# main.net
KiCad netlist of a schematic drawn in Altium Designer
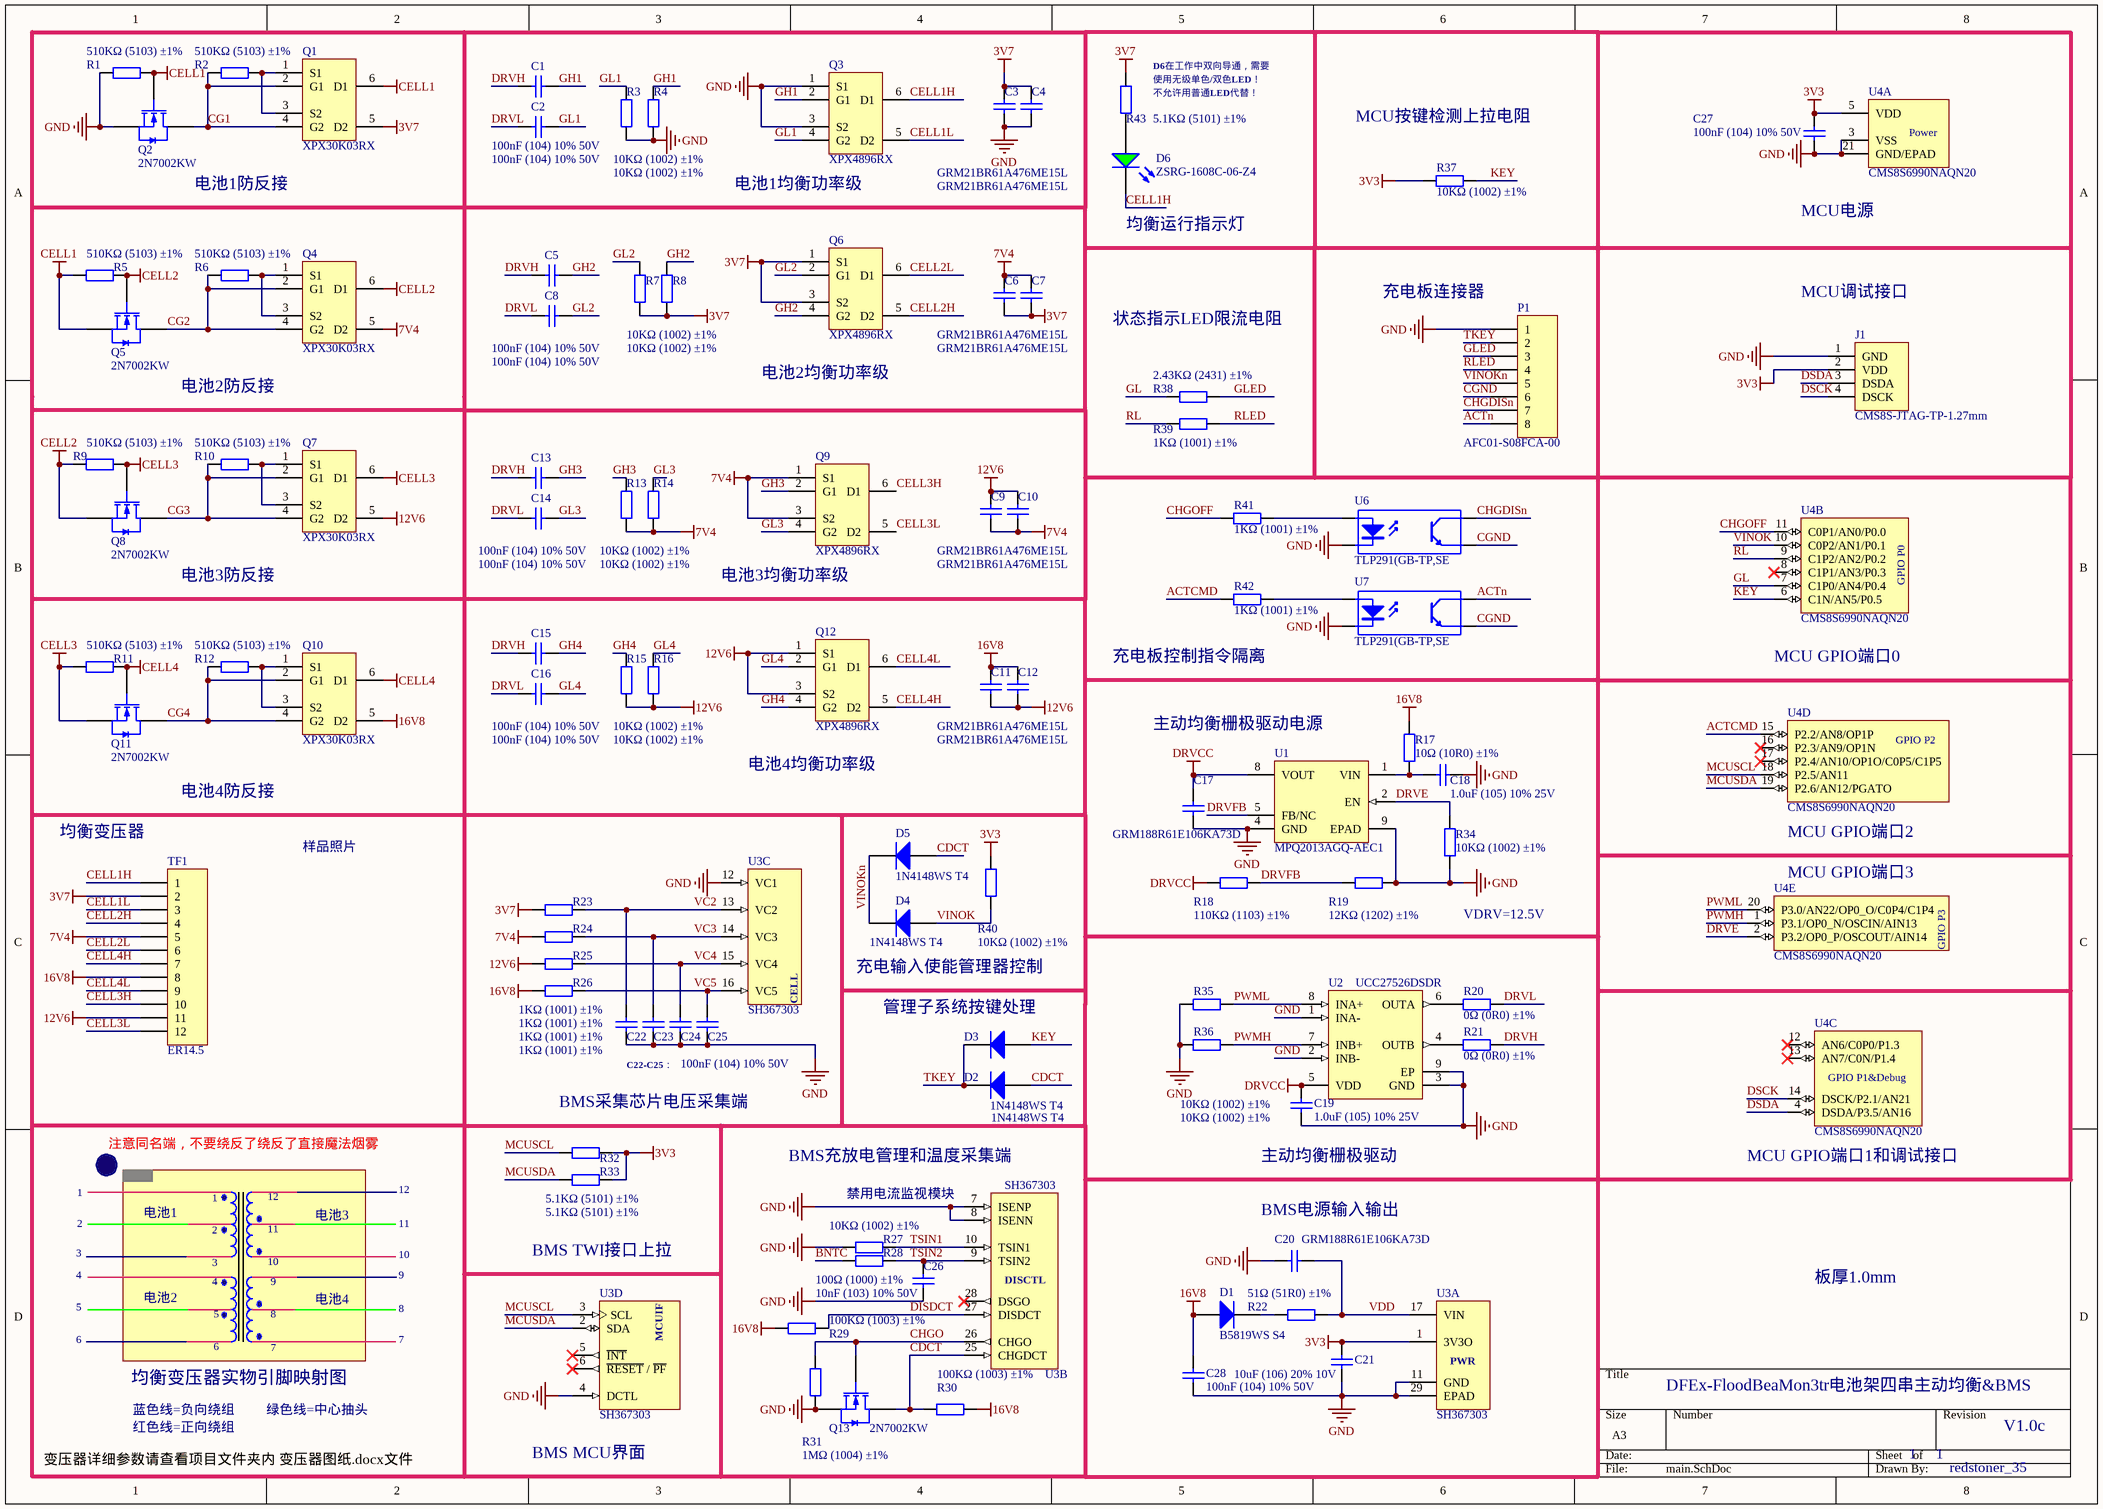
[diagram p0: main.SchDoc]

(export (version "E")
  (design (tool "Eeschema 10.0.6"))
  (components
    (comp (ref "C1")
      (value "100nF (104) 10% 50V")
      (footprint "0402_C")
      (description "贴片电容")
      (libsource (lib "Miscellaneous Devices LC") (part "0402 100nF (104) 10% 16V"))
    )
    (comp (ref "C2")
      (value "100nF (104) 10% 50V")
      (footprint "0402_C")
      (description "贴片电容")
      (libsource (lib "Miscellaneous Devices LC") (part "0402 100nF (104) 10% 16V"))
    )
    (comp (ref "C3")
      (value "GRM21BR61A476ME15L")
      (footprint "0805_C")
      (description "贴片MLCC电容，47uF (476) 20% 10V")
      (libsource (lib "Miscellaneous Devices LC") (part "0805 22uF (226) 20% 25V"))
    )
    (comp (ref "C4")
      (value "GRM21BR61A476ME15L")
      (footprint "0805_C")
      (description "贴片MLCC电容，47uF (476) 20% 10V")
      (libsource (lib "Miscellaneous Devices LC") (part "0805 22uF (226) 20% 25V"))
    )
    (comp (ref "C5")
      (value "100nF (104) 10% 50V")
      (footprint "0402_C")
      (description "贴片电容")
      (libsource (lib "Miscellaneous Devices LC") (part "0402 100nF (104) 10% 16V"))
    )
    (comp (ref "C6")
      (value "GRM21BR61A476ME15L")
      (footprint "0805_C")
      (description "贴片MLCC电容，47uF (476) 20% 10V")
      (libsource (lib "Miscellaneous Devices LC") (part "0805 22uF (226) 20% 25V"))
    )
    (comp (ref "C7")
      (value "GRM21BR61A476ME15L")
      (footprint "0805_C")
      (description "贴片MLCC电容，47uF (476) 20% 10V")
      (libsource (lib "Miscellaneous Devices LC") (part "0805 22uF (226) 20% 25V"))
    )
    (comp (ref "C8")
      (value "100nF (104) 10% 50V")
      (footprint "0402_C")
      (description "贴片电容")
      (libsource (lib "Miscellaneous Devices LC") (part "0402 100nF (104) 10% 16V"))
    )
    (comp (ref "C9")
      (value "GRM21BR61A476ME15L")
      (footprint "0805_C")
      (description "贴片MLCC电容，47uF (476) 20% 10V")
      (libsource (lib "Miscellaneous Devices LC") (part "0805 22uF (226) 20% 25V"))
    )
    (comp (ref "C10")
      (value "GRM21BR61A476ME15L")
      (footprint "0805_C")
      (description "贴片MLCC电容，47uF (476) 20% 10V")
      (libsource (lib "Miscellaneous Devices LC") (part "0805 22uF (226) 20% 25V"))
    )
    (comp (ref "C11")
      (value "GRM21BR61A476ME15L")
      (footprint "0805_C")
      (description "贴片MLCC电容，47uF (476) 20% 10V")
      (libsource (lib "Miscellaneous Devices LC") (part "0805 22uF (226) 20% 25V"))
    )
    (comp (ref "C12")
      (value "GRM21BR61A476ME15L")
      (footprint "0805_C")
      (description "贴片MLCC电容，47uF (476) 20% 10V")
      (libsource (lib "Miscellaneous Devices LC") (part "0805 22uF (226) 20% 25V"))
    )
    (comp (ref "C13")
      (value "100nF (104) 10% 50V")
      (footprint "0402_C")
      (description "贴片电容")
      (libsource (lib "Miscellaneous Devices LC") (part "0402 100nF (104) 10% 16V"))
    )
    (comp (ref "C14")
      (value "100nF (104) 10% 50V")
      (footprint "0402_C")
      (description "贴片电容")
      (libsource (lib "Miscellaneous Devices LC") (part "0402 100nF (104) 10% 16V"))
    )
    (comp (ref "C15")
      (value "100nF (104) 10% 50V")
      (footprint "0402_C")
      (description "贴片电容")
      (libsource (lib "Miscellaneous Devices LC") (part "0402 100nF (104) 10% 16V"))
    )
    (comp (ref "C16")
      (value "100nF (104) 10% 50V")
      (footprint "0402_C")
      (description "贴片电容")
      (libsource (lib "Miscellaneous Devices LC") (part "0402 100nF (104) 10% 16V"))
    )
    (comp (ref "C17")
      (value "GRM188R61E106KA73D")
      (footprint "0603_C")
      (description "0603贴片MLCC电容 10uF ±20% 25V X5R")
      (libsource (lib "Miscellaneous Devices LC") (part "0603 10uF (106) 10% 10V"))
    )
    (comp (ref "C18")
      (value "1.0uF (105) 10% 25V")
      (footprint "0402_C")
      (description "贴片电容")
      (libsource (lib "Miscellaneous Devices LC") (part "0402 1.0uF (105) 10% 25V"))
    )
    (comp (ref "C19")
      (value "1.0uF (105) 10% 25V")
      (footprint "0402_C")
      (description "贴片电容")
      (libsource (lib "Miscellaneous Devices LC") (part "0402 1.0uF (105) 10% 25V"))
    )
    (comp (ref "C20")
      (value "GRM188R61E106KA73D")
      (footprint "0603_C")
      (description "0603贴片MLCC电容 10uF ±20% 25V X5R")
      (libsource (lib "Miscellaneous Devices LC") (part "0603 2.2uF (225) 10% 16V"))
    )
    (comp (ref "C21")
      (value "10uF (106) 20% 10V")
      (footprint "0402_C")
      (description "贴片电容")
      (libsource (lib "Miscellaneous Devices LC") (part "0402 10uF (106) 20% 6.3V"))
    )
    (comp (ref "C22")
      (value "100nF (104) 10% 50V")
      (footprint "0402_C")
      (description "贴片电容")
      (libsource (lib "Miscellaneous Devices LC") (part "0402 100nF (104) 10% 16V"))
    )
    (comp (ref "C23")
      (value "100nF (104) 10% 50V")
      (footprint "0402_C")
      (description "贴片电容")
      (libsource (lib "Miscellaneous Devices LC") (part "0402 100nF (104) 10% 16V"))
    )
    (comp (ref "C24")
      (value "100nF (104) 10% 50V")
      (footprint "0402_C")
      (description "贴片电容")
      (libsource (lib "Miscellaneous Devices LC") (part "0402 100nF (104) 10% 16V"))
    )
    (comp (ref "C25")
      (value "100nF (104) 10% 50V")
      (footprint "0402_C")
      (description "贴片电容")
      (libsource (lib "Miscellaneous Devices LC") (part "0402 100nF (104) 10% 16V"))
    )
    (comp (ref "C26")
      (value "10nF (103) 10% 50V")
      (footprint "0402_C")
      (description "贴片电容")
      (libsource (lib "Miscellaneous Devices LC") (part "0402 10nF (103) 10% 50V"))
    )
    (comp (ref "C27")
      (value "100nF (104) 10% 50V")
      (footprint "0402_C")
      (description "贴片电容")
      (libsource (lib "Miscellaneous Devices LC") (part "0402 100nF (104) 10% 16V"))
    )
    (comp (ref "C28")
      (value "100nF (104) 10% 50V")
      (footprint "0402_C")
      (description "贴片电容")
      (libsource (lib "Miscellaneous Devices LC") (part "0402 100nF (104) 10% 16V"))
    )
    (comp (ref "D1")
      (value "B5819WS S4")
      (footprint "SOD-323")
      (description "二极管")
      (libsource (lib "Miscellaneous Devices LC") (part "SOD-323 1N4148WS T4"))
    )
    (comp (ref "D2")
      (value "1N4148WS T4")
      (footprint "SOD-323")
      (description "二极管")
      (libsource (lib "Miscellaneous Devices LC") (part "SOD-323 1N4148WS T4"))
    )
    (comp (ref "D3")
      (value "1N4148WS T4")
      (footprint "SOD-323")
      (description "二极管")
      (libsource (lib "Miscellaneous Devices LC") (part "SOD-323 1N4148WS T4"))
    )
    (comp (ref "D4")
      (value "1N4148WS T4")
      (footprint "SOD-323")
      (description "二极管")
      (libsource (lib "Miscellaneous Devices LC") (part "SOD-323 1N4148WS T4"))
    )
    (comp (ref "D5")
      (value "1N4148WS T4")
      (footprint "SOD-323")
      (description "二极管")
      (libsource (lib "Miscellaneous Devices LC") (part "SOD-323 1N4148WS T4"))
    )
    (comp (ref "D6")
      (value "ZSRG-1608C-06-Z4")
      (footprint "0603_LED_S1")
      (description "发光二极管 红绿无级双色")
      (libsource (lib "Miscellaneous Devices LC") (part "0603 绿灯"))
    )
    (comp (ref "J1")
      (value "CMS8S-JTAG-TP-1.27mm")
      (footprint "CMS8S-JTAG-TP-1.27")
      (description "面向CMS8S6990NA单片机的调试贴片触点，并不是元器件实物")
      (libsource (lib "custom") (part "CMS8S-JTAG-TP-1.27mm"))
    )
    (comp (ref "P1")
      (value "AFC01-S08FCA-00")
      (footprint "FPC0.5 2H-WS-8P")
      (description "翻盖式下接FPC/FFC连接器 P数:8P 间距:0.5mm")
      (fields (field (name "PUBLISHER") "Altium Limited"))
      (libsource (lib "山猫的集成库20190318") (part "CON 8"))
    )
    (comp (ref "Q1")
      (value "XPX30K03RX")
      (footprint "EDFN3x3")
      (description "双P沟道MOSFET, DFN3x3 -20V -30A 12mΩ")
      (libsource (lib "custom") (part "XPX10H03RX"))
    )
    (comp (ref "Q2")
      (value "2N7002KW")
      (footprint "SC70-3")
      (description "单N沟道MOSFET(场效应管)")
      (libsource (lib "Miscellaneous Devices LC") (part "2N7002 7002"))
    )
    (comp (ref "Q3")
      (value "XPX4896RX")
      (footprint "EDFN3x3")
      (description "双N沟道MOSFET, DFN3x3 40V 45A 7.2mΩ")
      (libsource (lib "custom") (part "XPX10H03RX"))
    )
    (comp (ref "Q4")
      (value "XPX30K03RX")
      (footprint "EDFN3x3")
      (description "双P沟道MOSFET, DFN3x3 -20V -30A 12mΩ")
      (libsource (lib "custom") (part "XPX10H03RX"))
    )
    (comp (ref "Q5")
      (value "2N7002KW")
      (footprint "SC70-3")
      (description "单N沟道MOSFET(场效应管)")
      (libsource (lib "Miscellaneous Devices LC") (part "2N7002 7002"))
    )
    (comp (ref "Q6")
      (value "XPX4896RX")
      (footprint "EDFN3x3")
      (description "双N沟道MOSFET, DFN3x3 40V 45A 7.2mΩ")
      (libsource (lib "custom") (part "XPX10H03RX"))
    )
    (comp (ref "Q7")
      (value "XPX30K03RX")
      (footprint "EDFN3x3")
      (description "双P沟道MOSFET, DFN3x3 -20V -30A 12mΩ")
      (libsource (lib "custom") (part "XPX10H03RX"))
    )
    (comp (ref "Q8")
      (value "2N7002KW")
      (footprint "SC70-3")
      (description "单N沟道MOSFET(场效应管)")
      (libsource (lib "Miscellaneous Devices LC") (part "2N7002 7002"))
    )
    (comp (ref "Q9")
      (value "XPX4896RX")
      (footprint "EDFN3x3")
      (description "双N沟道MOSFET, DFN3x3 40V 45A 7.2mΩ")
      (libsource (lib "custom") (part "XPX10H03RX"))
    )
    (comp (ref "Q10")
      (value "XPX30K03RX")
      (footprint "EDFN3x3")
      (description "双P沟道MOSFET, DFN3x3 -20V -30A 12mΩ")
      (libsource (lib "custom") (part "XPX10H03RX"))
    )
    (comp (ref "Q11")
      (value "2N7002KW")
      (footprint "SC70-3")
      (description "单N沟道MOSFET(场效应管)")
      (libsource (lib "Miscellaneous Devices LC") (part "2N7002 7002"))
    )
    (comp (ref "Q12")
      (value "XPX4896RX")
      (footprint "EDFN3x3")
      (description "双N沟道MOSFET, DFN3x3 40V 45A 7.2mΩ")
      (libsource (lib "custom") (part "XPX10H03RX"))
    )
    (comp (ref "Q13")
      (value "2N7002KW")
      (footprint "SC70-3")
      (description "单N沟道MOSFET(场效应管)")
      (libsource (lib "Miscellaneous Devices LC") (part "2N7002 7002"))
    )
    (comp (ref "R1")
      (value "510KΩ (5103) ±1%")
      (footprint "0402_R")
      (description "贴片电阻")
      (libsource (lib "Miscellaneous Devices LC") (part "0402 510KΩ (5103) 1%"))
    )
    (comp (ref "R2")
      (value "510KΩ (5103) ±1%")
      (footprint "0402_R")
      (description "贴片电阻")
      (libsource (lib "Miscellaneous Devices LC") (part "0402 510KΩ (5103) 1%"))
    )
    (comp (ref "R3")
      (value "10KΩ (1002) ±1%")
      (footprint "0402_R")
      (description "贴片电阻")
      (libsource (lib "") (part "0402 10KΩ (1002) 1%_2"))
    )
    (comp (ref "R4")
      (value "10KΩ (1002) ±1%")
      (footprint "0402_R")
      (description "贴片电阻")
      (libsource (lib "") (part "0402 10KΩ (1002) 1%_2"))
    )
    (comp (ref "R5")
      (value "510KΩ (5103) ±1%")
      (footprint "0402_R")
      (description "贴片电阻")
      (libsource (lib "Miscellaneous Devices LC") (part "0402 510KΩ (5103) 1%"))
    )
    (comp (ref "R6")
      (value "510KΩ (5103) ±1%")
      (footprint "0402_R")
      (description "贴片电阻")
      (libsource (lib "Miscellaneous Devices LC") (part "0402 510KΩ (5103) 1%"))
    )
    (comp (ref "R7")
      (value "10KΩ (1002) ±1%")
      (footprint "0402_R")
      (description "贴片电阻")
      (libsource (lib "Miscellaneous Devices LC") (part "0402 10KΩ (1002) 1%"))
    )
    (comp (ref "R8")
      (value "10KΩ (1002) ±1%")
      (footprint "0402_R")
      (description "贴片电阻")
      (libsource (lib "Miscellaneous Devices LC") (part "0402 10KΩ (1002) 1%"))
    )
    (comp (ref "R9")
      (value "510KΩ (5103) ±1%")
      (footprint "0402_R")
      (description "贴片电阻")
      (libsource (lib "Miscellaneous Devices LC") (part "0402 510KΩ (5103) 1%"))
    )
    (comp (ref "R10")
      (value "510KΩ (5103) ±1%")
      (footprint "0402_R")
      (description "贴片电阻")
      (libsource (lib "Miscellaneous Devices LC") (part "0402 510KΩ (5103) 1%"))
    )
    (comp (ref "R11")
      (value "510KΩ (5103) ±1%")
      (footprint "0402_R")
      (description "贴片电阻")
      (libsource (lib "Miscellaneous Devices LC") (part "0402 510KΩ (5103) 1%"))
    )
    (comp (ref "R12")
      (value "510KΩ (5103) ±1%")
      (footprint "0402_R")
      (description "贴片电阻")
      (libsource (lib "Miscellaneous Devices LC") (part "0402 510KΩ (5103) 1%"))
    )
    (comp (ref "R13")
      (value "10KΩ (1002) ±1%")
      (footprint "0402_R")
      (description "贴片电阻")
      (libsource (lib "Miscellaneous Devices LC") (part "0402 10KΩ (1002) 1%"))
    )
    (comp (ref "R14")
      (value "10KΩ (1002) ±1%")
      (footprint "0402_R")
      (description "贴片电阻")
      (libsource (lib "Miscellaneous Devices LC") (part "0402 10KΩ (1002) 1%"))
    )
    (comp (ref "R15")
      (value "10KΩ (1002) ±1%")
      (footprint "0402_R")
      (description "贴片电阻")
      (libsource (lib "Miscellaneous Devices LC") (part "0402 10KΩ (1002) 1%"))
    )
    (comp (ref "R16")
      (value "10KΩ (1002) ±1%")
      (footprint "0402_R")
      (description "贴片电阻")
      (libsource (lib "Miscellaneous Devices LC") (part "0402 10KΩ (1002) 1%"))
    )
    (comp (ref "R17")
      (value "10Ω (10R0) ±1%")
      (footprint "0402_R")
      (description "贴片电阻")
      (libsource (lib "Miscellaneous Devices LC") (part "0402 10Ω (10R0) 1%"))
    )
    (comp (ref "R18")
      (value "110KΩ (1103) ±1%")
      (footprint "0402_R")
      (description "贴片电阻")
      (libsource (lib "Miscellaneous Devices LC") (part "0402 100KΩ (1003) 1%"))
    )
    (comp (ref "R19")
      (value "12KΩ (1202) ±1%")
      (footprint "0402_R")
      (description "贴片电阻")
      (libsource (lib "Miscellaneous Devices LC") (part "0402 12KΩ (1202) 1%"))
    )
    (comp (ref "R20")
      (value "0Ω (0R0) ±1%")
      (footprint "0402_R")
      (description "贴片电阻")
      (libsource (lib "Miscellaneous Devices LC") (part "0402 0Ω (0R0) 1%"))
    )
    (comp (ref "R21")
      (value "0Ω (0R0) ±1%")
      (footprint "0402_R")
      (description "贴片电阻")
      (libsource (lib "Miscellaneous Devices LC") (part "0402 0Ω (0R0) 1%"))
    )
    (comp (ref "R22")
      (value "51Ω (51R0) ±1%")
      (footprint "0603_R")
      (description "贴片电阻")
      (libsource (lib "Miscellaneous Devices LC") (part "0603 51Ω (51R0) 1%"))
    )
    (comp (ref "R23")
      (value "1KΩ (1001) ±1%")
      (footprint "0402_R")
      (description "贴片电阻")
      (libsource (lib "Miscellaneous Devices LC") (part "0402 1KΩ (1001) 1%"))
    )
    (comp (ref "R24")
      (value "1KΩ (1001) ±1%")
      (footprint "0402_R")
      (description "贴片电阻")
      (libsource (lib "Miscellaneous Devices LC") (part "0402 1KΩ (1001) 1%"))
    )
    (comp (ref "R25")
      (value "1KΩ (1001) ±1%")
      (footprint "0402_R")
      (description "贴片电阻")
      (libsource (lib "Miscellaneous Devices LC") (part "0402 1KΩ (1001) 1%"))
    )
    (comp (ref "R26")
      (value "1KΩ (1001) ±1%")
      (footprint "0402_R")
      (description "贴片电阻")
      (libsource (lib "Miscellaneous Devices LC") (part "0402 1KΩ (1001) 1%"))
    )
    (comp (ref "R27")
      (value "10KΩ (1002) ±1%")
      (footprint "0402_R")
      (description "贴片电阻")
      (libsource (lib "") (part "0402 10KΩ (1002) 1%_1"))
    )
    (comp (ref "R28")
      (value "100Ω (1000) ±1%")
      (footprint "0402_R")
      (description "贴片电阻")
      (libsource (lib "Miscellaneous Devices LC") (part "0402 100Ω (1000) 1%"))
    )
    (comp (ref "R29")
      (value "100KΩ (1003) ±1%")
      (footprint "0402_R")
      (description "贴片电阻")
      (libsource (lib "Miscellaneous Devices LC") (part "0402 100KΩ (1003) 1%"))
    )
    (comp (ref "R30")
      (value "100KΩ (1003) ±1%")
      (footprint "0402_R")
      (description "贴片电阻")
      (libsource (lib "") (part "0402 100KΩ (1003) 1%_1"))
    )
    (comp (ref "R31")
      (value "1MΩ (1004) ±1%")
      (footprint "0402_R")
      (description "贴片电阻")
      (libsource (lib "Miscellaneous Devices LC") (part "0402 1MΩ (1004) 1%"))
    )
    (comp (ref "R32")
      (value "5.1KΩ (5101) ±1%")
      (footprint "0402_R")
      (description "贴片电阻")
      (libsource (lib "Miscellaneous Devices LC") (part "0402 5.1KΩ (5101) 1%"))
    )
    (comp (ref "R33")
      (value "5.1KΩ (5101) ±1%")
      (footprint "0402_R")
      (description "贴片电阻")
      (libsource (lib "Miscellaneous Devices LC") (part "0402 5.1KΩ (5101) 1%"))
    )
    (comp (ref "R34")
      (value "10KΩ (1002) ±1%")
      (footprint "0402_R")
      (description "贴片电阻")
      (libsource (lib "Miscellaneous Devices LC") (part "0402 10KΩ (1002) 1%"))
    )
    (comp (ref "R35")
      (value "10KΩ (1002) ±1%")
      (footprint "0402_R")
      (description "贴片电阻")
      (libsource (lib "") (part "0402 10KΩ (1002) 1%_1"))
    )
    (comp (ref "R36")
      (value "10KΩ (1002) ±1%")
      (footprint "0402_R")
      (description "贴片电阻")
      (libsource (lib "") (part "0402 10KΩ (1002) 1%_1"))
    )
    (comp (ref "R37")
      (value "10KΩ (1002) ±1%")
      (footprint "0402_R")
      (description "贴片电阻")
      (libsource (lib "") (part "0402 10KΩ (1002) 1%_3"))
    )
    (comp (ref "R38")
      (value "2.43KΩ (2431) ±1%")
      (footprint "0402_R")
      (description "贴片电阻")
      (libsource (lib "") (part "0402 2KΩ (2001) 1%_1"))
    )
    (comp (ref "R39")
      (value "1KΩ (1001) ±1%")
      (footprint "0402_R")
      (description "贴片电阻")
      (libsource (lib "Miscellaneous Devices LC") (part "0402 1KΩ (1001) 1%"))
    )
    (comp (ref "R40")
      (value "10KΩ (1002) ±1%")
      (footprint "0402_R")
      (description "贴片电阻")
      (libsource (lib "Miscellaneous Devices LC") (part "0402 10KΩ (1002) 1%"))
    )
    (comp (ref "R41")
      (value "1KΩ (1001) ±1%")
      (footprint "0402_R")
      (description "贴片电阻")
      (libsource (lib "Miscellaneous Devices LC") (part "0402 1KΩ (1001) 1%"))
    )
    (comp (ref "R42")
      (value "1KΩ (1001) ±1%")
      (footprint "0402_R")
      (description "贴片电阻")
      (libsource (lib "Miscellaneous Devices LC") (part "0402 1KΩ (1001) 1%"))
    )
    (comp (ref "R43")
      (value "5.1KΩ (5101) ±1%")
      (footprint "0402_R")
      (description "贴片电阻")
      (libsource (lib "Miscellaneous Devices LC") (part "0402 2KΩ (2001) 1%"))
    )
    (comp (ref "TF1")
      (value "ER14.5")
      (footprint "ER14.5 SMT6+6")
      (description "ER14.5定制均衡变压器，PC40磁芯")
      (fields (field (name "PUBLISHER") "Altium Limited"))
      (libsource (lib "山猫的集成库20190318") (part "CON 12"))
    )
    (comp (ref "U1")
      (value "MPQ2013AGQ-AEC1")
      (footprint "MPQ2013A-QFN8")
      (description "MPS 40V LDO with Enable pin QFN3x3 package")
      (libsource (lib "custom") (part "MPQ2013AGQ-xx-AEC1"))
    )
    (comp (ref "U2")
      (value "UCC27526DSDR")
      (footprint "DSD0008D")
      (description "双路18V 5A峰值电流低侧栅极驱动器，WSON-8封装尺寸")
      (libsource (lib "custom") (part "UCC27526DSDR"))
    )
    (comp (ref "U3")
      (value "SH367303")
      (footprint "QFN28-5x5")
      (description "3至5串锂离子电池BMS模拟前端，具备充放电控制/电压采集和I2C接口")
      (libsource (lib "custom") (part "SH367303"))
    )
    (comp (ref "U4")
      (value "CMS8S6990NAQN20")
      (footprint "QFN40P300X300X800_HS-21N")
      (description "增强型闪存1T 8051单片机，16KB Flash 256+1K XRAM")
      (libsource (lib "custom") (part "CM8S6990NA-QFN20"))
    )
    (comp (ref "U6")
      (value "TLP291(GB-TP,SE")
      (footprint "SOP127P700X210-4M")
      (description "DC输入光电耦合隔离器，线性输入输出，隔离电压(rms):3750V SOP-4小型封装")
      (fields (field (name "PUBLISHER") "Altium Limited"))
      (libsource (lib "Miscellaneous Devices") (part "Optoisolator1"))
    )
    (comp (ref "U7")
      (value "TLP291(GB-TP,SE")
      (footprint "SOP127P700X210-4M")
      (description "DC输入光电耦合隔离器，线性输入输出，隔离电压(rms):3750V SOP-4小型封装")
      (fields (field (name "PUBLISHER") "Altium Limited"))
      (libsource (lib "Miscellaneous Devices") (part "Optoisolator1"))
    )
  )
  (nets
    (net (code "1") (name "/ACTCMD") (class "Default")
      (node (ref "R42") (pin "1") (pinfunction "1_1") (pintype "passive"))
      (node (ref "U4") (pin "15") (pinfunction "P2.2/AN8/OP1P_15") (pintype "bidirectional"))
    )
    (net (code "2") (name "/ACTn") (class "Default")
      (node (ref "P1") (pin "8") (pinfunction "8_8") (pintype "passive"))
      (node (ref "U7") (pin "4") (pinfunction "C_4") (pintype "passive"))
    )
    (net (code "3") (name "/BNTC") (class "Default")
      (node (ref "R28") (pin "1") (pinfunction "1_1") (pintype "passive"))
    )
    (net (code "4") (name "/CDCT") (class "Default")
      (node (ref "D2") (pin "1") (pinfunction "A_1") (pintype "passive"))
      (node (ref "D5") (pin "1") (pinfunction "A_1") (pintype "passive"))
      (node (ref "Q13") (pin "3") (pinfunction "D_3") (pintype "passive"))
      (node (ref "R30") (pin "2") (pinfunction "2_2") (pintype "passive"))
      (node (ref "U3") (pin "25") (pinfunction "CHGDCT_25") (pintype "input"))
    )
    (net (code "5") (name "/CELL1H") (class "Default")
      (node (ref "D6") (pin "K") (pinfunction "K_K") (pintype "passive"))
      (node (ref "Q3") (pin "6") (pinfunction "D1_6") (pintype "passive"))
      (node (ref "TF1") (pin "1") (pinfunction "1_1") (pintype "passive"))
    )
    (net (code "6") (name "/CELL1L") (class "Default")
      (node (ref "Q3") (pin "5") (pinfunction "D2_5") (pintype "passive"))
      (node (ref "TF1") (pin "3") (pinfunction "3_3") (pintype "passive"))
    )
    (net (code "7") (name "/CELL2H") (class "Default")
      (node (ref "Q6") (pin "5") (pinfunction "D2_5") (pintype "passive"))
      (node (ref "TF1") (pin "4") (pinfunction "4_4") (pintype "passive"))
    )
    (net (code "8") (name "/CELL2L") (class "Default")
      (node (ref "Q6") (pin "6") (pinfunction "D1_6") (pintype "passive"))
      (node (ref "TF1") (pin "6") (pinfunction "6_6") (pintype "passive"))
    )
    (net (code "9") (name "/CELL3H") (class "Default")
      (node (ref "Q9") (pin "6") (pinfunction "D1_6") (pintype "passive"))
      (node (ref "TF1") (pin "10") (pinfunction "10_10") (pintype "passive"))
    )
    (net (code "10") (name "/CELL3L") (class "Default")
      (node (ref "Q9") (pin "5") (pinfunction "D2_5") (pintype "passive"))
      (node (ref "TF1") (pin "12") (pinfunction "12_12") (pintype "passive"))
    )
    (net (code "11") (name "/CELL4H") (class "Default")
      (node (ref "Q12") (pin "5") (pinfunction "D2_5") (pintype "passive"))
      (node (ref "TF1") (pin "7") (pinfunction "7_7") (pintype "passive"))
    )
    (net (code "12") (name "/CELL4L") (class "Default")
      (node (ref "Q12") (pin "6") (pinfunction "D1_6") (pintype "passive"))
      (node (ref "TF1") (pin "9") (pinfunction "9_9") (pintype "passive"))
    )
    (net (code "13") (name "/CG1") (class "Default")
      (node (ref "Q1") (pin "2") (pinfunction "G1_2") (pintype "passive"))
      (node (ref "Q1") (pin "4") (pinfunction "G2_4") (pintype "passive"))
      (node (ref "Q2") (pin "3") (pinfunction "D_3") (pintype "passive"))
      (node (ref "R2") (pin "1") (pinfunction "1_1") (pintype "passive"))
    )
    (net (code "14") (name "/CG2") (class "Default")
      (node (ref "Q4") (pin "2") (pinfunction "G1_2") (pintype "passive"))
      (node (ref "Q4") (pin "4") (pinfunction "G2_4") (pintype "passive"))
      (node (ref "Q5") (pin "3") (pinfunction "D_3") (pintype "passive"))
      (node (ref "R6") (pin "1") (pinfunction "1_1") (pintype "passive"))
    )
    (net (code "15") (name "/CG3") (class "Default")
      (node (ref "Q7") (pin "2") (pinfunction "G1_2") (pintype "passive"))
      (node (ref "Q7") (pin "4") (pinfunction "G2_4") (pintype "passive"))
      (node (ref "Q8") (pin "3") (pinfunction "D_3") (pintype "passive"))
      (node (ref "R10") (pin "1") (pinfunction "1_1") (pintype "passive"))
    )
    (net (code "16") (name "/CG4") (class "Default")
      (node (ref "Q10") (pin "2") (pinfunction "G1_2") (pintype "passive"))
      (node (ref "Q10") (pin "4") (pinfunction "G2_4") (pintype "passive"))
      (node (ref "Q11") (pin "3") (pinfunction "D_3") (pintype "passive"))
      (node (ref "R12") (pin "1") (pinfunction "1_1") (pintype "passive"))
    )
    (net (code "17") (name "/CGND") (class "Default")
      (node (ref "P1") (pin "6") (pinfunction "6_6") (pintype "passive"))
      (node (ref "U6") (pin "3") (pinfunction "E_3") (pintype "passive"))
      (node (ref "U7") (pin "3") (pinfunction "E_3") (pintype "passive"))
    )
    (net (code "18") (name "/CHGDISn") (class "Default")
      (node (ref "P1") (pin "7") (pinfunction "7_7") (pintype "passive"))
      (node (ref "U6") (pin "4") (pinfunction "C_4") (pintype "passive"))
    )
    (net (code "19") (name "/CHGO") (class "Default")
      (node (ref "Q13") (pin "1") (pinfunction "G_1") (pintype "passive"))
      (node (ref "R31") (pin "2") (pinfunction "2_2") (pintype "passive"))
      (node (ref "U3") (pin "26") (pinfunction "CHGO_26") (pintype "output"))
    )
    (net (code "20") (name "/CHGOFF") (class "Default")
      (node (ref "R41") (pin "1") (pinfunction "1_1") (pintype "passive"))
      (node (ref "U4") (pin "11") (pinfunction "C0P1/AN0/P0.0_11") (pintype "bidirectional"))
    )
    (net (code "21") (name "/DISDCT") (class "Default")
      (node (ref "R29") (pin "2") (pinfunction "2_2") (pintype "passive"))
      (node (ref "U3") (pin "27") (pinfunction "DISDCT_27") (pintype "input"))
    )
    (net (code "22") (name "/DRVE") (class "Default")
      (node (ref "R34") (pin "2") (pinfunction "2_2") (pintype "passive"))
      (node (ref "U1") (pin "2") (pinfunction "EN_2") (pintype "input"))
      (node (ref "U4") (pin "2") (pinfunction "P3.2/OP0_P/OSCOUT/AIN14_2") (pintype "bidirectional"))
    )
    (net (code "23") (name "/DRVFB") (class "Default")
      (node (ref "R18") (pin "2") (pinfunction "2_2") (pintype "passive"))
      (node (ref "R19") (pin "1") (pinfunction "1_1") (pintype "passive"))
      (node (ref "U1") (pin "5") (pinfunction "FB/NC_5") (pintype "passive"))
    )
    (net (code "24") (name "/DRVH") (class "Default")
      (node (ref "C1") (pin "1") (pinfunction "1_1") (pintype "passive"))
      (node (ref "C13") (pin "1") (pinfunction "1_1") (pintype "passive"))
      (node (ref "C15") (pin "1") (pinfunction "1_1") (pintype "passive"))
      (node (ref "C5") (pin "1") (pinfunction "1_1") (pintype "passive"))
      (node (ref "R21") (pin "2") (pinfunction "2_2") (pintype "passive"))
    )
    (net (code "25") (name "/DRVL") (class "Default")
      (node (ref "C14") (pin "1") (pinfunction "1_1") (pintype "passive"))
      (node (ref "C16") (pin "1") (pinfunction "1_1") (pintype "passive"))
      (node (ref "C2") (pin "1") (pinfunction "1_1") (pintype "passive"))
      (node (ref "C8") (pin "1") (pinfunction "1_1") (pintype "passive"))
      (node (ref "R20") (pin "2") (pinfunction "2_2") (pintype "passive"))
    )
    (net (code "26") (name "/DSCK") (class "Default")
      (node (ref "J1") (pin "4") (pinfunction "DSCK_4") (pintype "passive"))
      (node (ref "U4") (pin "14") (pinfunction "DSCK/P2.1/AN21_14") (pintype "bidirectional"))
    )
    (net (code "27") (name "/DSDA") (class "Default")
      (node (ref "J1") (pin "3") (pinfunction "DSDA_3") (pintype "passive"))
      (node (ref "U4") (pin "4") (pinfunction "DSDA/P3.5/AN16_4") (pintype "bidirectional"))
    )
    (net (code "28") (name "/GH1") (class "Default")
      (node (ref "C1") (pin "2") (pinfunction "2_2") (pintype "passive"))
      (node (ref "Q3") (pin "2") (pinfunction "G1_2") (pintype "passive"))
      (node (ref "R4") (pin "1") (pinfunction "1_1") (pintype "passive"))
    )
    (net (code "29") (name "/GH2") (class "Default")
      (node (ref "C5") (pin "2") (pinfunction "2_2") (pintype "passive"))
      (node (ref "Q6") (pin "4") (pinfunction "G2_4") (pintype "passive"))
      (node (ref "R8") (pin "2") (pinfunction "2_2") (pintype "passive"))
    )
    (net (code "30") (name "/GH3") (class "Default")
      (node (ref "C13") (pin "2") (pinfunction "2_2") (pintype "passive"))
      (node (ref "Q9") (pin "2") (pinfunction "G1_2") (pintype "passive"))
      (node (ref "R13") (pin "2") (pinfunction "2_2") (pintype "passive"))
    )
    (net (code "31") (name "/GH4") (class "Default")
      (node (ref "C15") (pin "2") (pinfunction "2_2") (pintype "passive"))
      (node (ref "Q12") (pin "4") (pinfunction "G2_4") (pintype "passive"))
      (node (ref "R15") (pin "2") (pinfunction "2_2") (pintype "passive"))
    )
    (net (code "32") (name "/GL") (class "Default")
      (node (ref "R38") (pin "1") (pinfunction "1_1") (pintype "passive"))
      (node (ref "U4") (pin "7") (pinfunction "C1P0/AN4/P0.4_7") (pintype "bidirectional"))
    )
    (net (code "33") (name "/GL1") (class "Default")
      (node (ref "C2") (pin "2") (pinfunction "2_2") (pintype "passive"))
      (node (ref "Q3") (pin "4") (pinfunction "G2_4") (pintype "passive"))
      (node (ref "R3") (pin "1") (pinfunction "1_1") (pintype "passive"))
    )
    (net (code "34") (name "/GL2") (class "Default")
      (node (ref "C8") (pin "2") (pinfunction "2_2") (pintype "passive"))
      (node (ref "Q6") (pin "2") (pinfunction "G1_2") (pintype "passive"))
      (node (ref "R7") (pin "2") (pinfunction "2_2") (pintype "passive"))
    )
    (net (code "35") (name "/GL3") (class "Default")
      (node (ref "C14") (pin "2") (pinfunction "2_2") (pintype "passive"))
      (node (ref "Q9") (pin "4") (pinfunction "G2_4") (pintype "passive"))
      (node (ref "R14") (pin "2") (pinfunction "2_2") (pintype "passive"))
    )
    (net (code "36") (name "/GL4") (class "Default")
      (node (ref "C16") (pin "2") (pinfunction "2_2") (pintype "passive"))
      (node (ref "Q12") (pin "2") (pinfunction "G1_2") (pintype "passive"))
      (node (ref "R16") (pin "2") (pinfunction "2_2") (pintype "passive"))
    )
    (net (code "37") (name "/GLED") (class "Default")
      (node (ref "P1") (pin "3") (pinfunction "3_3") (pintype "passive"))
      (node (ref "R38") (pin "2") (pinfunction "2_2") (pintype "passive"))
    )
    (net (code "38") (name "/KEY") (class "Default")
      (node (ref "D3") (pin "1") (pinfunction "A_1") (pintype "passive"))
      (node (ref "R37") (pin "2") (pinfunction "2_2") (pintype "passive"))
      (node (ref "U4") (pin "6") (pinfunction "C1N/AN5/P0.5_6") (pintype "bidirectional"))
    )
    (net (code "39") (name "/MCUSCL") (class "Default")
      (node (ref "R32") (pin "1") (pinfunction "1_1") (pintype "passive"))
      (node (ref "U3") (pin "3") (pinfunction "SCL_3") (pintype "input"))
      (node (ref "U4") (pin "18") (pinfunction "P2.5/AN11_18") (pintype "bidirectional"))
    )
    (net (code "40") (name "/MCUSDA") (class "Default")
      (node (ref "R33") (pin "1") (pinfunction "1_1") (pintype "passive"))
      (node (ref "U3") (pin "2") (pinfunction "SDA_2") (pintype "bidirectional"))
      (node (ref "U4") (pin "19") (pinfunction "P2.6/AN12/PGATO_19") (pintype "bidirectional"))
    )
    (net (code "41") (name "/PWMH") (class "Default")
      (node (ref "R36") (pin "1") (pinfunction "1_1") (pintype "passive"))
      (node (ref "U2") (pin "7") (pinfunction "INB+_7") (pintype "input"))
      (node (ref "U4") (pin "1") (pinfunction "P3.1/OP0_N/OSCIN/AIN13_1") (pintype "bidirectional"))
    )
    (net (code "42") (name "/PWML") (class "Default")
      (node (ref "R35") (pin "1") (pinfunction "1_1") (pintype "passive"))
      (node (ref "U2") (pin "8") (pinfunction "INA+_8") (pintype "input"))
      (node (ref "U4") (pin "20") (pinfunction "P3.0/AN22/OP0_O/C0P4/C1P4_20") (pintype "bidirectional"))
    )
    (net (code "43") (name "/RL") (class "Default")
      (node (ref "R39") (pin "1") (pinfunction "1_1") (pintype "passive"))
      (node (ref "U4") (pin "9") (pinfunction "C1P2/AN2/P0.2_9") (pintype "bidirectional"))
    )
    (net (code "44") (name "/RLED") (class "Default")
      (node (ref "P1") (pin "4") (pinfunction "4_4") (pintype "passive"))
      (node (ref "R39") (pin "2") (pinfunction "2_2") (pintype "passive"))
    )
    (net (code "45") (name "/TKEY") (class "Default")
      (node (ref "D2") (pin "2") (pinfunction "K_2") (pintype "passive"))
      (node (ref "D3") (pin "2") (pinfunction "K_2") (pintype "passive"))
      (node (ref "P1") (pin "2") (pinfunction "2_2") (pintype "passive"))
    )
    (net (code "46") (name "/TSIN1") (class "Default")
      (node (ref "R27") (pin "1") (pinfunction "1_1") (pintype "passive"))
      (node (ref "U3") (pin "10") (pinfunction "TSIN1_10") (pintype "input"))
    )
    (net (code "47") (name "/TSIN2") (class "Default")
      (node (ref "C26") (pin "2") (pinfunction "2_2") (pintype "passive"))
      (node (ref "R28") (pin "2") (pinfunction "2_2") (pintype "passive"))
      (node (ref "U3") (pin "9") (pinfunction "TSIN2_9") (pintype "input"))
    )
    (net (code "48") (name "/VC2") (class "Default")
      (node (ref "C22") (pin "2") (pinfunction "2_2") (pintype "passive"))
      (node (ref "R23") (pin "2") (pinfunction "2_2") (pintype "passive"))
      (node (ref "U3") (pin "13") (pinfunction "VC2_13") (pintype "input"))
    )
    (net (code "49") (name "/VC3") (class "Default")
      (node (ref "C23") (pin "2") (pinfunction "2_2") (pintype "passive"))
      (node (ref "R24") (pin "2") (pinfunction "2_2") (pintype "passive"))
      (node (ref "U3") (pin "14") (pinfunction "VC3_14") (pintype "input"))
    )
    (net (code "50") (name "/VC4") (class "Default")
      (node (ref "C24") (pin "2") (pinfunction "2_2") (pintype "passive"))
      (node (ref "R25") (pin "2") (pinfunction "2_2") (pintype "passive"))
      (node (ref "U3") (pin "15") (pinfunction "VC4_15") (pintype "input"))
    )
    (net (code "51") (name "/VC5") (class "Default")
      (node (ref "C25") (pin "2") (pinfunction "2_2") (pintype "passive"))
      (node (ref "R26") (pin "2") (pinfunction "2_2") (pintype "passive"))
      (node (ref "U3") (pin "16") (pinfunction "VC5_16") (pintype "input"))
    )
    (net (code "52") (name "/VDD") (class "Default")
      (node (ref "C20") (pin "2") (pinfunction "2_2") (pintype "passive"))
      (node (ref "R22") (pin "2") (pinfunction "2_2") (pintype "passive"))
      (node (ref "U3") (pin "17") (pinfunction "VIN_17") (pintype "power_in"))
    )
    (net (code "53") (name "/VINOK") (class "Default")
      (node (ref "D4") (pin "1") (pinfunction "A_1") (pintype "passive"))
      (node (ref "R40") (pin "1") (pinfunction "1_1") (pintype "passive"))
      (node (ref "U4") (pin "10") (pinfunction "C0P2/AN1/P0.1_10") (pintype "bidirectional"))
    )
    (net (code "54") (name "/VINOKn") (class "Default")
      (node (ref "D4") (pin "2") (pinfunction "K_2") (pintype "passive"))
      (node (ref "D5") (pin "2") (pinfunction "K_2") (pintype "passive"))
      (node (ref "P1") (pin "5") (pinfunction "5_5") (pintype "passive"))
    )
    (net (code "55") (name "3V3") (class "Default")
      (node (ref "C21") (pin "2") (pinfunction "2_2") (pintype "passive"))
      (node (ref "C27") (pin "2") (pinfunction "2_2") (pintype "passive"))
      (node (ref "J1") (pin "2") (pinfunction "VDD_2") (pintype "passive"))
      (node (ref "R32") (pin "2") (pinfunction "2_2") (pintype "passive"))
      (node (ref "R33") (pin "2") (pinfunction "2_2") (pintype "passive"))
      (node (ref "R37") (pin "1") (pinfunction "1_1") (pintype "passive"))
      (node (ref "R40") (pin "2") (pinfunction "2_2") (pintype "passive"))
      (node (ref "U3") (pin "1") (pinfunction "3V3O_1") (pintype "power_in"))
      (node (ref "U4") (pin "5") (pinfunction "VDD_5") (pintype "power_in"))
    )
    (net (code "56") (name "3V7") (class "Default")
      (node (ref "C3") (pin "2") (pinfunction "2_2") (pintype "passive"))
      (node (ref "C4") (pin "2") (pinfunction "2_2") (pintype "passive"))
      (node (ref "C6") (pin "1") (pinfunction "1_1") (pintype "passive"))
      (node (ref "C7") (pin "1") (pinfunction "1_1") (pintype "passive"))
      (node (ref "Q1") (pin "5") (pinfunction "D2_5") (pintype "passive"))
      (node (ref "Q6") (pin "1") (pinfunction "S1_1") (pintype "passive"))
      (node (ref "Q6") (pin "3") (pinfunction "S2_3") (pintype "passive"))
      (node (ref "R23") (pin "1") (pinfunction "1_1") (pintype "passive"))
      (node (ref "R43") (pin "2") (pinfunction "2_2") (pintype "passive"))
      (node (ref "R7") (pin "1") (pinfunction "1_1") (pintype "passive"))
      (node (ref "R8") (pin "1") (pinfunction "1_1") (pintype "passive"))
      (node (ref "TF1") (pin "2") (pinfunction "2_2") (pintype "passive"))
    )
    (net (code "57") (name "7V4") (class "Default")
      (node (ref "C10") (pin "1") (pinfunction "1_1") (pintype "passive"))
      (node (ref "C6") (pin "2") (pinfunction "2_2") (pintype "passive"))
      (node (ref "C7") (pin "2") (pinfunction "2_2") (pintype "passive"))
      (node (ref "C9") (pin "1") (pinfunction "1_1") (pintype "passive"))
      (node (ref "Q4") (pin "5") (pinfunction "D2_5") (pintype "passive"))
      (node (ref "Q9") (pin "1") (pinfunction "S1_1") (pintype "passive"))
      (node (ref "Q9") (pin "3") (pinfunction "S2_3") (pintype "passive"))
      (node (ref "R13") (pin "1") (pinfunction "1_1") (pintype "passive"))
      (node (ref "R14") (pin "1") (pinfunction "1_1") (pintype "passive"))
      (node (ref "R24") (pin "1") (pinfunction "1_1") (pintype "passive"))
      (node (ref "TF1") (pin "5") (pinfunction "5_5") (pintype "passive"))
    )
    (net (code "58") (name "12V6") (class "Default")
      (node (ref "C10") (pin "2") (pinfunction "2_2") (pintype "passive"))
      (node (ref "C11") (pin "1") (pinfunction "1_1") (pintype "passive"))
      (node (ref "C12") (pin "1") (pinfunction "1_1") (pintype "passive"))
      (node (ref "C9") (pin "2") (pinfunction "2_2") (pintype "passive"))
      (node (ref "Q12") (pin "1") (pinfunction "S1_1") (pintype "passive"))
      (node (ref "Q12") (pin "3") (pinfunction "S2_3") (pintype "passive"))
      (node (ref "Q7") (pin "5") (pinfunction "D2_5") (pintype "passive"))
      (node (ref "R15") (pin "1") (pinfunction "1_1") (pintype "passive"))
      (node (ref "R16") (pin "1") (pinfunction "1_1") (pintype "passive"))
      (node (ref "R25") (pin "1") (pinfunction "1_1") (pintype "passive"))
      (node (ref "TF1") (pin "11") (pinfunction "11_11") (pintype "passive"))
    )
    (net (code "59") (name "16V8") (class "Default")
      (node (ref "C11") (pin "2") (pinfunction "2_2") (pintype "passive"))
      (node (ref "C12") (pin "2") (pinfunction "2_2") (pintype "passive"))
      (node (ref "C28") (pin "2") (pinfunction "2_2") (pintype "passive"))
      (node (ref "D1") (pin "1") (pinfunction "A_1") (pintype "passive"))
      (node (ref "Q10") (pin "5") (pinfunction "D2_5") (pintype "passive"))
      (node (ref "R17") (pin "2") (pinfunction "2_2") (pintype "passive"))
      (node (ref "R26") (pin "1") (pinfunction "1_1") (pintype "passive"))
      (node (ref "R29") (pin "1") (pinfunction "1_1") (pintype "passive"))
      (node (ref "R30") (pin "1") (pinfunction "1_1") (pintype "passive"))
      (node (ref "TF1") (pin "8") (pinfunction "8_8") (pintype "passive"))
    )
    (net (code "60") (name "CELL1") (class "Default")
      (node (ref "Q1") (pin "6") (pinfunction "D1_6") (pintype "passive"))
      (node (ref "Q2") (pin "1") (pinfunction "G_1") (pintype "passive"))
      (node (ref "Q5") (pin "2") (pinfunction "S_2") (pintype "passive"))
      (node (ref "R1") (pin "2") (pinfunction "2_2") (pintype "passive"))
      (node (ref "R5") (pin "1") (pinfunction "1_1") (pintype "passive"))
    )
    (net (code "61") (name "CELL2") (class "Default")
      (node (ref "Q4") (pin "6") (pinfunction "D1_6") (pintype "passive"))
      (node (ref "Q5") (pin "1") (pinfunction "G_1") (pintype "passive"))
      (node (ref "Q8") (pin "2") (pinfunction "S_2") (pintype "passive"))
      (node (ref "R5") (pin "2") (pinfunction "2_2") (pintype "passive"))
      (node (ref "R9") (pin "1") (pinfunction "1_1") (pintype "passive"))
    )
    (net (code "62") (name "CELL3") (class "Default")
      (node (ref "Q11") (pin "2") (pinfunction "S_2") (pintype "passive"))
      (node (ref "Q7") (pin "6") (pinfunction "D1_6") (pintype "passive"))
      (node (ref "Q8") (pin "1") (pinfunction "G_1") (pintype "passive"))
      (node (ref "R11") (pin "1") (pinfunction "1_1") (pintype "passive"))
      (node (ref "R9") (pin "2") (pinfunction "2_2") (pintype "passive"))
    )
    (net (code "63") (name "CELL4") (class "Default")
      (node (ref "Q10") (pin "6") (pinfunction "D1_6") (pintype "passive"))
      (node (ref "Q11") (pin "1") (pinfunction "G_1") (pintype "passive"))
      (node (ref "R11") (pin "2") (pinfunction "2_2") (pintype "passive"))
    )
    (net (code "64") (name "DRVCC") (class "Default")
      (node (ref "C17") (pin "2") (pinfunction "2_2") (pintype "passive"))
      (node (ref "C19") (pin "2") (pinfunction "2_2") (pintype "passive"))
      (node (ref "R18") (pin "1") (pinfunction "1_1") (pintype "passive"))
      (node (ref "U1") (pin "8") (pinfunction "VOUT_8") (pintype "passive"))
      (node (ref "U2") (pin "5") (pinfunction "VDD_5") (pintype "power_in"))
    )
    (net (code "65") (name "GND") (class "Default")
      (node (ref "C17") (pin "1") (pinfunction "1_1") (pintype "passive"))
      (node (ref "C18") (pin "2") (pinfunction "2_2") (pintype "passive"))
      (node (ref "C19") (pin "1") (pinfunction "1_1") (pintype "passive"))
      (node (ref "C20") (pin "1") (pinfunction "1_1") (pintype "passive"))
      (node (ref "C21") (pin "1") (pinfunction "1_1") (pintype "passive"))
      (node (ref "C22") (pin "1") (pinfunction "1_1") (pintype "passive"))
      (node (ref "C23") (pin "1") (pinfunction "1_1") (pintype "passive"))
      (node (ref "C24") (pin "1") (pinfunction "1_1") (pintype "passive"))
      (node (ref "C25") (pin "1") (pinfunction "1_1") (pintype "passive"))
      (node (ref "C26") (pin "1") (pinfunction "1_1") (pintype "passive"))
      (node (ref "C27") (pin "1") (pinfunction "1_1") (pintype "passive"))
      (node (ref "C28") (pin "1") (pinfunction "1_1") (pintype "passive"))
      (node (ref "C3") (pin "1") (pinfunction "1_1") (pintype "passive"))
      (node (ref "C4") (pin "1") (pinfunction "1_1") (pintype "passive"))
      (node (ref "J1") (pin "1") (pinfunction "GND_1") (pintype "passive"))
      (node (ref "P1") (pin "1") (pinfunction "1_1") (pintype "passive"))
      (node (ref "Q13") (pin "2") (pinfunction "S_2") (pintype "passive"))
      (node (ref "Q2") (pin "2") (pinfunction "S_2") (pintype "passive"))
      (node (ref "Q3") (pin "1") (pinfunction "S1_1") (pintype "passive"))
      (node (ref "Q3") (pin "3") (pinfunction "S2_3") (pintype "passive"))
      (node (ref "R1") (pin "1") (pinfunction "1_1") (pintype "passive"))
      (node (ref "R19") (pin "2") (pinfunction "2_2") (pintype "passive"))
      (node (ref "R27") (pin "2") (pinfunction "2_2") (pintype "passive"))
      (node (ref "R3") (pin "2") (pinfunction "2_2") (pintype "passive"))
      (node (ref "R31") (pin "1") (pinfunction "1_1") (pintype "passive"))
      (node (ref "R34") (pin "1") (pinfunction "1_1") (pintype "passive"))
      (node (ref "R35") (pin "2") (pinfunction "2_2") (pintype "passive"))
      (node (ref "R36") (pin "2") (pinfunction "2_2") (pintype "passive"))
      (node (ref "R4") (pin "2") (pinfunction "2_2") (pintype "passive"))
      (node (ref "U1") (pin "4") (pinfunction "GND_4") (pintype "power_in"))
      (node (ref "U1") (pin "9") (pinfunction "EPAD_9") (pintype "passive"))
      (node (ref "U2") (pin "1") (pinfunction "INA-_1") (pintype "input"))
      (node (ref "U2") (pin "2") (pinfunction "INB-_2") (pintype "input"))
      (node (ref "U2") (pin "3") (pinfunction "GND_3") (pintype "power_in"))
      (node (ref "U2") (pin "9") (pinfunction "EP_9") (pintype "power_in"))
      (node (ref "U3") (pin "11") (pinfunction "GND_11") (pintype "power_in"))
      (node (ref "U3") (pin "12") (pinfunction "VC1_12") (pintype "input"))
      (node (ref "U3") (pin "29") (pinfunction "EPAD_29") (pintype "power_in"))
      (node (ref "U3") (pin "4") (pinfunction "DCTL_4") (pintype "input"))
      (node (ref "U3") (pin "7") (pinfunction "ISENP_7") (pintype "input"))
      (node (ref "U3") (pin "8") (pinfunction "ISENN_8") (pintype "input"))
      (node (ref "U4") (pin "21") (pinfunction "GND/EPAD_21") (pintype "power_in"))
      (node (ref "U4") (pin "3") (pinfunction "VSS_3") (pintype "power_in"))
      (node (ref "U6") (pin "2") (pinfunction "K_2") (pintype "passive"))
      (node (ref "U7") (pin "2") (pinfunction "K_2") (pintype "passive"))
    )
    (net (code "66") (name "Net-(D1-K)") (class "Default")
      (node (ref "D1") (pin "2") (pinfunction "K_2") (pintype "passive"))
      (node (ref "R22") (pin "1") (pinfunction "1_1") (pintype "passive"))
    )
    (net (code "67") (name "Net-(D6-PadA)") (class "Default")
      (node (ref "D6") (pin "A") (pinfunction "A_A") (pintype "passive"))
      (node (ref "R43") (pin "1") (pinfunction "1_1") (pintype "passive"))
    )
    (net (code "68") (name "Net-(Q1-S1)") (class "Default")
      (node (ref "Q1") (pin "1") (pinfunction "S1_1") (pintype "passive"))
      (node (ref "Q1") (pin "3") (pinfunction "S2_3") (pintype "passive"))
      (node (ref "R2") (pin "2") (pinfunction "2_2") (pintype "passive"))
    )
    (net (code "69") (name "Net-(Q4-S1)") (class "Default")
      (node (ref "Q4") (pin "1") (pinfunction "S1_1") (pintype "passive"))
      (node (ref "Q4") (pin "3") (pinfunction "S2_3") (pintype "passive"))
      (node (ref "R6") (pin "2") (pinfunction "2_2") (pintype "passive"))
    )
    (net (code "70") (name "Net-(Q7-S1)") (class "Default")
      (node (ref "Q7") (pin "1") (pinfunction "S1_1") (pintype "passive"))
      (node (ref "Q7") (pin "3") (pinfunction "S2_3") (pintype "passive"))
      (node (ref "R10") (pin "2") (pinfunction "2_2") (pintype "passive"))
    )
    (net (code "71") (name "Net-(Q10-S1)") (class "Default")
      (node (ref "Q10") (pin "1") (pinfunction "S1_1") (pintype "passive"))
      (node (ref "Q10") (pin "3") (pinfunction "S2_3") (pintype "passive"))
      (node (ref "R12") (pin "2") (pinfunction "2_2") (pintype "passive"))
    )
    (net (code "72") (name "Net-(U1-VIN)") (class "Default")
      (node (ref "C18") (pin "1") (pinfunction "1_1") (pintype "passive"))
      (node (ref "R17") (pin "1") (pinfunction "1_1") (pintype "passive"))
      (node (ref "U1") (pin "1") (pinfunction "VIN_1") (pintype "power_in"))
    )
    (net (code "73") (name "Net-(U2-OUTA)") (class "Default")
      (node (ref "R20") (pin "1") (pinfunction "1_1") (pintype "passive"))
      (node (ref "U2") (pin "6") (pinfunction "OUTA_6") (pintype "output"))
    )
    (net (code "74") (name "Net-(U2-OUTB)") (class "Default")
      (node (ref "R21") (pin "1") (pinfunction "1_1") (pintype "passive"))
      (node (ref "U2") (pin "4") (pinfunction "OUTB_4") (pintype "output"))
    )
    (net (code "75") (name "Net-(U6-A)") (class "Default")
      (node (ref "R41") (pin "2") (pinfunction "2_2") (pintype "passive"))
      (node (ref "U6") (pin "1") (pinfunction "A_1") (pintype "passive"))
    )
    (net (code "76") (name "Net-(U7-A)") (class "Default")
      (node (ref "R42") (pin "2") (pinfunction "2_2") (pintype "passive"))
      (node (ref "U7") (pin "1") (pinfunction "A_1") (pintype "passive"))
    )
    (net (code "77") (name "unconnected-(U3B-DSGO-Pad28)") (class "Default")
      (node (ref "U3") (pin "28") (pinfunction "DSGO_28") (pintype "output+no_connect"))
    )
    (net (code "78") (name "unconnected-(U3D-~{INT}-Pad5)") (class "Default")
      (node (ref "U3") (pin "5") (pinfunction "~{INT}_5") (pintype "output+no_connect"))
    )
    (net (code "79") (name "unconnected-(U3D-~{RESET}_{slash}_~{PF}-Pad6)") (class "Default")
      (node (ref "U3") (pin "6") (pinfunction "~{RESET}_/_~{PF}_6") (pintype "output+no_connect"))
    )
    (net (code "80") (name "unconnected-(U4B-C1P1{slash}AN3{slash}P0.3-Pad8)") (class "Default")
      (node (ref "U4") (pin "8") (pinfunction "C1P1/AN3/P0.3_8") (pintype "bidirectional+no_connect"))
    )
    (net (code "81") (name "unconnected-(U4C-AN6{slash}C0P0{slash}P1.3-Pad12)") (class "Default")
      (node (ref "U4") (pin "12") (pinfunction "AN6/C0P0/P1.3_12") (pintype "bidirectional+no_connect"))
    )
    (net (code "82") (name "unconnected-(U4C-AN7{slash}C0N{slash}P1.4-Pad13)") (class "Default")
      (node (ref "U4") (pin "13") (pinfunction "AN7/C0N/P1.4_13") (pintype "bidirectional+no_connect"))
    )
    (net (code "83") (name "unconnected-(U4D-P2.3{slash}AN9{slash}OP1N-Pad16)") (class "Default")
      (node (ref "U4") (pin "16") (pinfunction "P2.3/AN9/OP1N_16") (pintype "bidirectional+no_connect"))
    )
    (net (code "84") (name "unconnected-(U4D-P2.4{slash}AN10{slash}OP1O{slash}C0P5{slash}C1P5-Pad17)") (class "Default")
      (node (ref "U4") (pin "17") (pinfunction "P2.4/AN10/OP1O/C0P5/C1P5_17") (pintype "bidirectional+no_connect"))
    )
  )
)
